# Digital_Output.net
KiCad netlist of a schematic drawn in Altium Designer
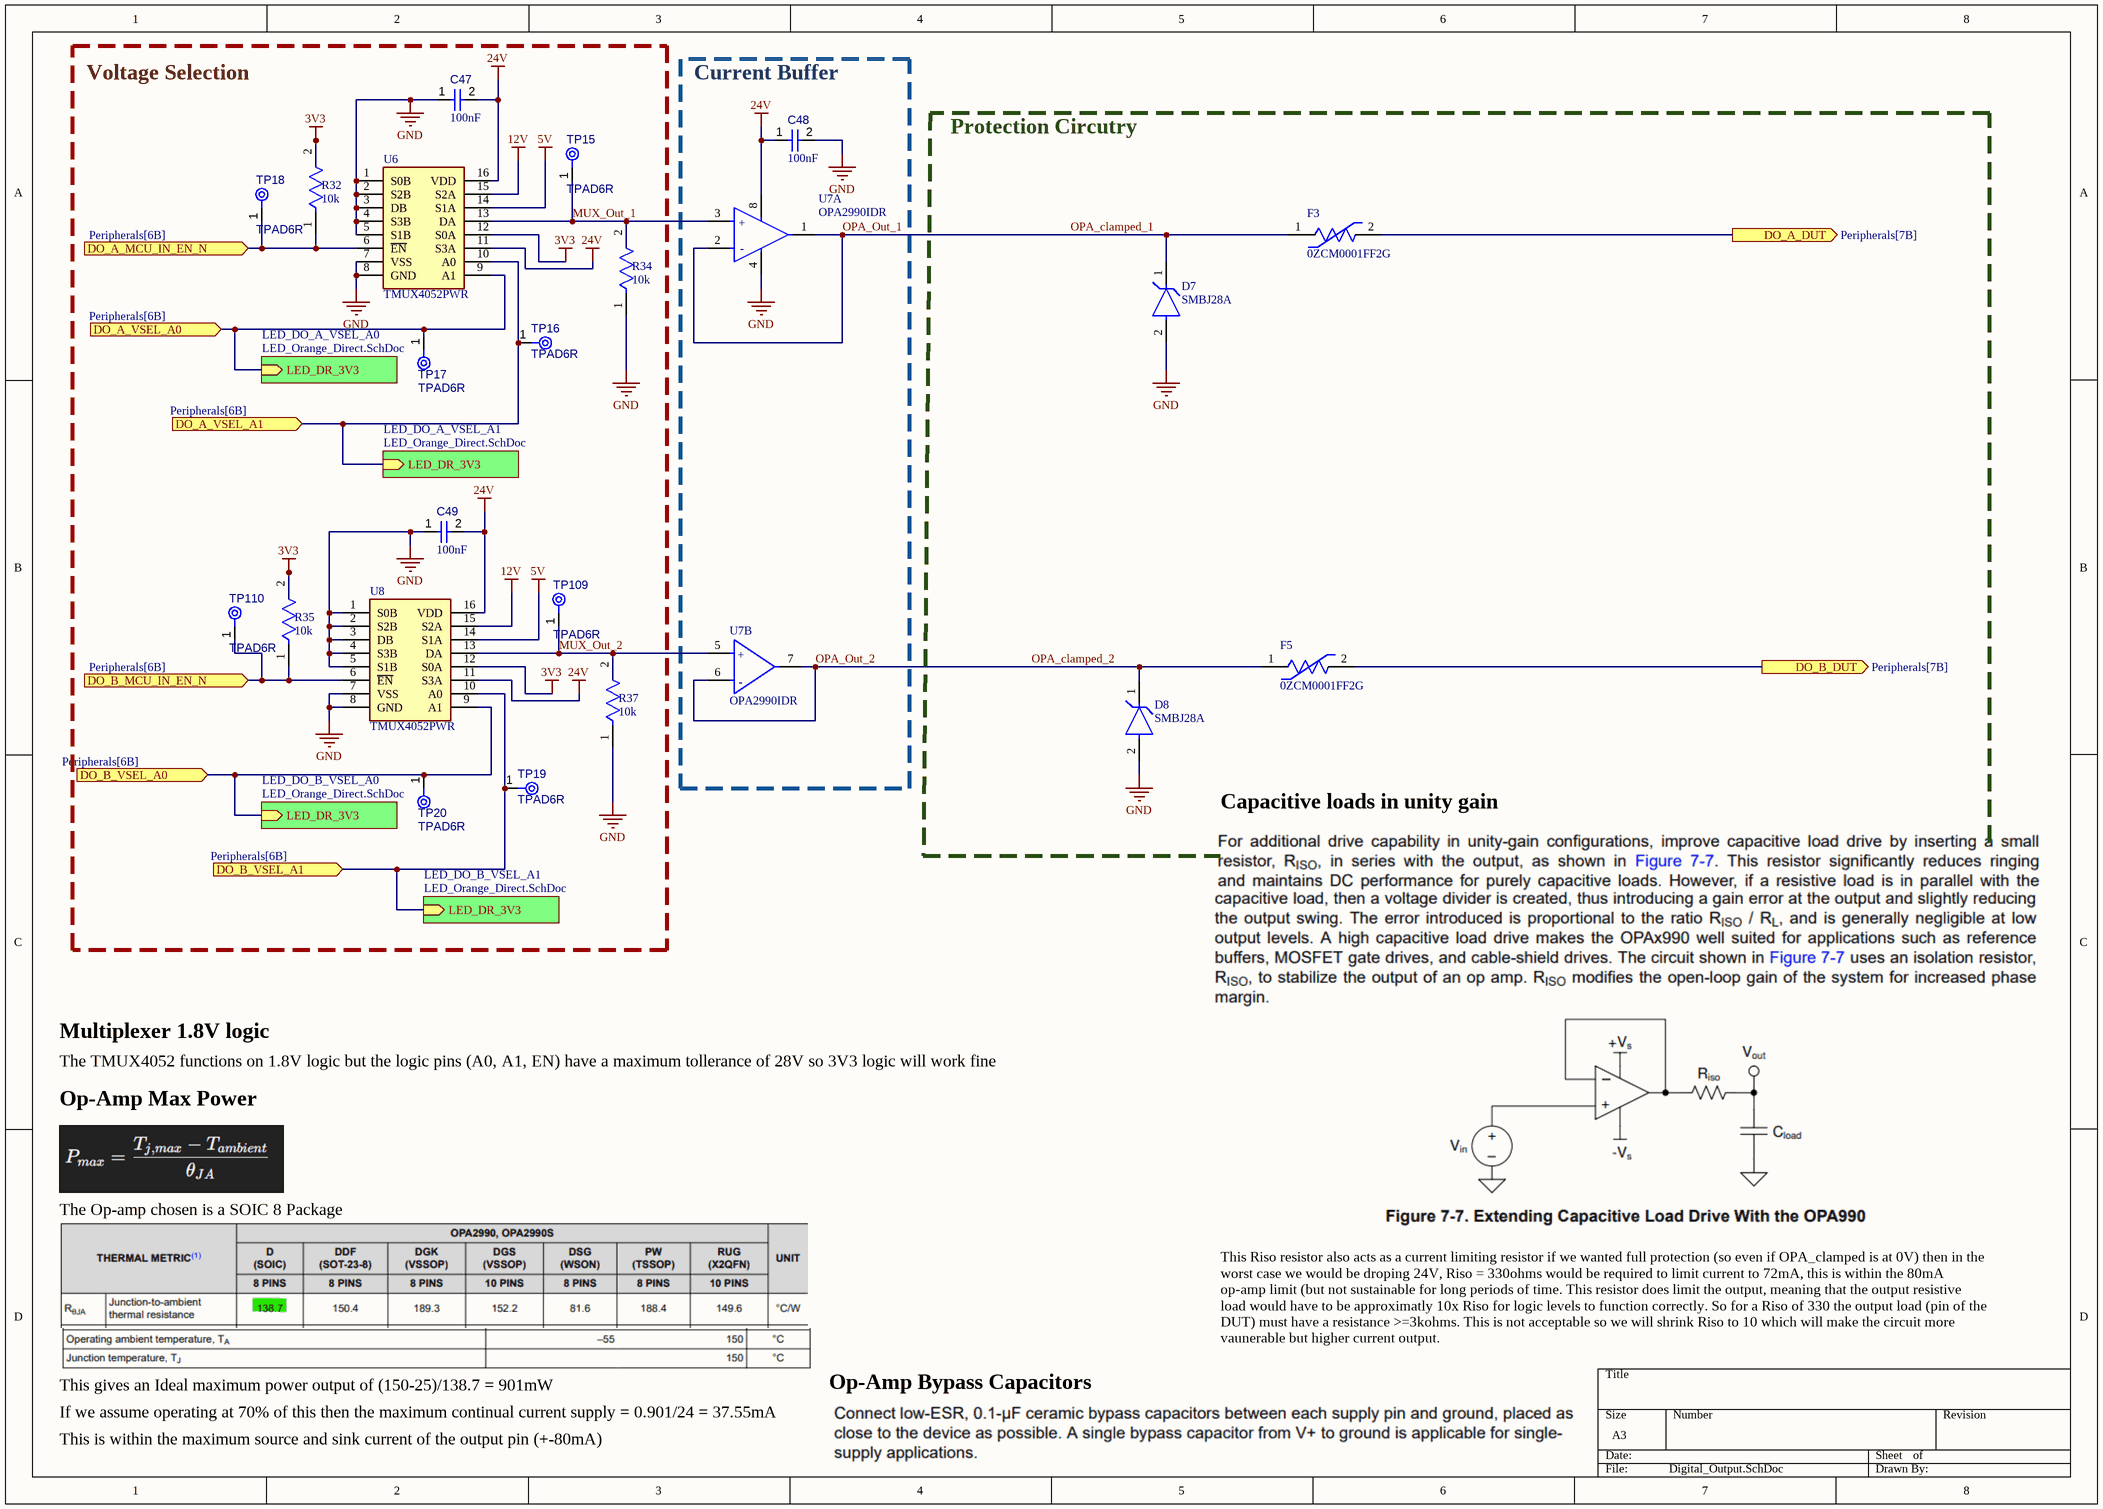
[diagram p0:  Digital_Output.SchDoc]

(export (version "E")
  (design (tool "Eeschema 10.0.6"))
  (components
    (comp (ref "C47")
      (value "100nF")
      (footprint "CAPC1608X90X40NL10T20")
      (description "Chip Capacitor, 100 nF, +/- 10%, 50 V, 0603 (1608 Metric)")
      (fields (field (name "TOLERANCE") "10%") (field (name "Comment") "Capacitor 100 nF +/-10% 50 V 0603"))
      (libsource (lib "HIL RIG FYP") (part "CAP-NP-2"))
    )
    (comp (ref "C48")
      (value "100nF")
      (footprint "CAPC1608X90X40NL10T20")
      (description "Chip Capacitor, 100 nF, +/- 10%, 50 V, 0603 (1608 Metric)")
      (fields (field (name "TOLERANCE") "10%") (field (name "Comment") "Capacitor 100 nF +/-10% 50 V 0603"))
      (libsource (lib "HIL RIG FYP") (part "CAP-NP-2"))
    )
    (comp (ref "C49")
      (value "100nF")
      (footprint "CAPC1608X90X40NL10T20")
      (description "Chip Capacitor, 100 nF, +/- 10%, 50 V, 0603 (1608 Metric)")
      (fields (field (name "TOLERANCE") "10%") (field (name "Comment") "Capacitor 100 nF +/-10% 50 V 0603"))
      (libsource (lib "HIL RIG FYP") (part "CAP-NP-2"))
    )
    (comp (ref "D7")
      (value "SMBJ28A")
      (footprint "FP-SMBJ-MFG")
      (description "Tvs Diodes & Esd Suppressors; SMBJ28A; Littelfuse; 28 V; 45.4 V; 31.1 V; 31.1 V")
      (fields (field (name "VOLTAGE") "28V"))
      (libsource (lib "HIL RIG FYP") (part "f813f71cba58e380607f5dd3caf9714"))
    )
    (comp (ref "D8")
      (value "SMBJ28A")
      (footprint "FP-SMBJ-MFG")
      (description "Tvs Diodes & Esd Suppressors; SMBJ28A; Littelfuse; 28 V; 45.4 V; 31.1 V; 31.1 V")
      (fields (field (name "VOLTAGE") "28V"))
      (libsource (lib "HIL RIG FYP") (part "f813f71cba58e380607f5dd3caf9714"))
    )
    (comp (ref "F3")
      (value "0ZCM0001FF2G")
      (footprint "FP-0ZCM0001FF2G-MFG")
      (description "Prices include import duty and tax. RESETTABLE PTC FUSE, SMD, 0603 SIZE, 10MA, 60V;")
      (libsource (lib "HIL RIG FYP") (part "1c6d77a0208143737455a0c7eb396be"))
    )
    (comp (ref "F5")
      (value "0ZCM0001FF2G")
      (footprint "FP-0ZCM0001FF2G-MFG")
      (description "Prices include import duty and tax. RESETTABLE PTC FUSE, SMD, 0603 SIZE, 10MA, 60V;")
      (libsource (lib "HIL RIG FYP") (part "1c6d77a0208143737455a0c7eb396be"))
    )
    (comp (ref "R32")
      (value "10k")
      (footprint "FP-RT0603-IPC_C")
      (description "Res Thin Film 0603 10K Ohm 0.1% 1/10W ¦25ppm/¦C SMD Paper T/R")
      (fields (field (name "TOLERANCE") "0.1%") (field (name "Comment") "RT0603BRD0710KL"))
      (libsource (lib "HIL RIG FYP") (part "1029c3af85768c4190bb7ad29bc67b5"))
    )
    (comp (ref "R34")
      (value "10k")
      (footprint "FP-RT0603-IPC_C")
      (description "Res Thin Film 0603 10K Ohm 0.1% 1/10W ¦25ppm/¦C SMD Paper T/R")
      (fields (field (name "TOLERANCE") "0.1%") (field (name "Comment") "RT0603BRD0710KL"))
      (libsource (lib "HIL RIG FYP") (part "1029c3af85768c4190bb7ad29bc67b5"))
    )
    (comp (ref "R35")
      (value "10k")
      (footprint "FP-RT0603-IPC_C")
      (description "Res Thin Film 0603 10K Ohm 0.1% 1/10W ¦25ppm/¦C SMD Paper T/R")
      (fields (field (name "TOLERANCE") "0.1%") (field (name "Comment") "RT0603BRD0710KL"))
      (libsource (lib "HIL RIG FYP") (part "1029c3af85768c4190bb7ad29bc67b5"))
    )
    (comp (ref "R37")
      (value "10k")
      (footprint "FP-RT0603-IPC_C")
      (description "Res Thin Film 0603 10K Ohm 0.1% 1/10W ¦25ppm/¦C SMD Paper T/R")
      (fields (field (name "TOLERANCE") "0.1%") (field (name "Comment") "RT0603BRD0710KL"))
      (libsource (lib "HIL RIG FYP") (part "1029c3af85768c4190bb7ad29bc67b5"))
    )
    (comp (ref "TP15")
      (value "TPAD6R")
      (footprint "TP06R")
      (description "0.6mm round")
      (libsource (lib "HIL RIG FYP") (part "CMP-001-0001-4"))
    )
    (comp (ref "TP16")
      (value "TPAD6R")
      (footprint "TP06R")
      (description "0.6mm round")
      (libsource (lib "HIL RIG FYP") (part "CMP-001-0001-4"))
    )
    (comp (ref "TP17")
      (value "TPAD6R")
      (footprint "TP06R")
      (description "0.6mm round")
      (libsource (lib "HIL RIG FYP") (part "CMP-001-0001-4"))
    )
    (comp (ref "TP18")
      (value "TPAD6R")
      (footprint "TP06R")
      (description "0.6mm round")
      (libsource (lib "HIL RIG FYP") (part "CMP-001-0001-4"))
    )
    (comp (ref "TP19")
      (value "TPAD6R")
      (footprint "TP06R")
      (description "0.6mm round")
      (libsource (lib "HIL RIG FYP") (part "CMP-001-0001-4"))
    )
    (comp (ref "TP20")
      (value "TPAD6R")
      (footprint "TP06R")
      (description "0.6mm round")
      (libsource (lib "HIL RIG FYP") (part "CMP-001-0001-4"))
    )
    (comp (ref "TP109")
      (value "TPAD6R")
      (footprint "TP06R")
      (description "0.6mm round")
      (libsource (lib "HIL RIG FYP") (part "CMP-001-0001-4"))
    )
    (comp (ref "TP110")
      (value "TPAD6R")
      (footprint "TP06R")
      (description "0.6mm round")
      (libsource (lib "HIL RIG FYP") (part "CMP-001-0001-4"))
    )
    (comp (ref "U6")
      (value "TMUX4052PWR")
      (footprint "SOP65P640X120-16N")
      (description "Texas Instruments")
      (fields (field (name "MOUSER PART NUMBER") "595-TMUX4052PWR"))
      (libsource (lib "HIL RIG FYP") (part "TMUX4052PWR"))
    )
    (comp (ref "U7")
      (value "OPA2990IDR")
      (footprint "FP-D0008A-IPC_A")
      (description "IC OPAMP GP 2 CIRCUIT 8SOIC / General Purpose Amplifier 2 Circuit Rail-to-Rail 8-SOIC")
      (libsource (lib "HIL RIG FYP") (part "d5b36c1049528187b1d2197d5d58d7e"))
    )
    (comp (ref "U8")
      (value "TMUX4052PWR")
      (footprint "SOP65P640X120-16N")
      (description "Texas Instruments")
      (fields (field (name "MOUSER PART NUMBER") "595-TMUX4052PWR"))
      (libsource (lib "HIL RIG FYP") (part "TMUX4052PWR"))
    )
  )
  (nets
    (net (code "1") (name "/DO_A_DUT") (class "Default")
      (node (ref "F3") (pin "2") (pinfunction "2_2") (pintype "passive"))
    )
    (net (code "2") (name "/DO_A_MCU_IN_EN_N") (class "Default")
      (node (ref "R32") (pin "1") (pinfunction "1_1") (pintype "passive"))
      (node (ref "TP18") (pin "1") (pinfunction "TP_1") (pintype "passive"))
      (node (ref "U6") (pin "6") (pinfunction "~{EN}_6") (pintype "passive"))
    )
    (net (code "3") (name "/DO_A_VSEL_A0") (class "Default")
      (node (ref "TP17") (pin "1") (pinfunction "TP_1") (pintype "passive"))
      (node (ref "U6") (pin "9") (pinfunction "A1_9") (pintype "passive"))
    )
    (net (code "4") (name "/DO_A_VSEL_A1") (class "Default")
      (node (ref "TP16") (pin "1") (pinfunction "TP_1") (pintype "passive"))
      (node (ref "U6") (pin "10") (pinfunction "A0_10") (pintype "passive"))
    )
    (net (code "5") (name "/DO_B_DUT") (class "Default")
      (node (ref "F5") (pin "2") (pinfunction "2_2") (pintype "passive"))
    )
    (net (code "6") (name "/DO_B_MCU_IN_EN_N") (class "Default")
      (node (ref "R35") (pin "1") (pinfunction "1_1") (pintype "passive"))
      (node (ref "TP110") (pin "1") (pinfunction "TP_1") (pintype "passive"))
      (node (ref "U8") (pin "6") (pinfunction "~{EN}_6") (pintype "passive"))
    )
    (net (code "7") (name "/DO_B_VSEL_A0") (class "Default")
      (node (ref "TP20") (pin "1") (pinfunction "TP_1") (pintype "passive"))
      (node (ref "U8") (pin "9") (pinfunction "A1_9") (pintype "passive"))
    )
    (net (code "8") (name "/DO_B_VSEL_A1") (class "Default")
      (node (ref "TP19") (pin "1") (pinfunction "TP_1") (pintype "passive"))
      (node (ref "U8") (pin "10") (pinfunction "A0_10") (pintype "passive"))
    )
    (net (code "9") (name "/MUX_Out_1") (class "Default")
      (node (ref "R34") (pin "2") (pinfunction "2_2") (pintype "passive"))
      (node (ref "TP15") (pin "1") (pinfunction "TP_1") (pintype "passive"))
      (node (ref "U6") (pin "13") (pinfunction "DA_13") (pintype "passive"))
      (node (ref "U7") (pin "3") (pinfunction "IN1+_3") (pintype "tri_state"))
    )
    (net (code "10") (name "/MUX_Out_2") (class "Default")
      (node (ref "R37") (pin "2") (pinfunction "2_2") (pintype "passive"))
      (node (ref "TP109") (pin "1") (pinfunction "TP_1") (pintype "passive"))
      (node (ref "U7") (pin "5") (pinfunction "IN2+_5") (pintype "tri_state"))
      (node (ref "U8") (pin "13") (pinfunction "DA_13") (pintype "passive"))
    )
    (net (code "11") (name "/OPA_Out_1") (class "Default")
      (node (ref "D7") (pin "1") (pinfunction "C_1") (pintype "passive"))
      (node (ref "F3") (pin "1") (pinfunction "1_1") (pintype "passive"))
      (node (ref "U7") (pin "1") (pinfunction "OUT1_1") (pintype "passive"))
      (node (ref "U7") (pin "2") (pinfunction "IN1-_2") (pintype "tri_state"))
    )
    (net (code "12") (name "/OPA_Out_2") (class "Default")
      (node (ref "D8") (pin "1") (pinfunction "C_1") (pintype "passive"))
      (node (ref "F5") (pin "1") (pinfunction "1_1") (pintype "passive"))
      (node (ref "U7") (pin "6") (pinfunction "IN2-_6") (pintype "tri_state"))
      (node (ref "U7") (pin "7") (pinfunction "OUT2_7") (pintype "passive"))
    )
    (net (code "13") (name "3V3") (class "Default")
      (node (ref "R32") (pin "2") (pinfunction "2_2") (pintype "passive"))
      (node (ref "R35") (pin "2") (pinfunction "2_2") (pintype "passive"))
      (node (ref "U6") (pin "12") (pinfunction "S0A_12") (pintype "passive"))
      (node (ref "U8") (pin "12") (pinfunction "S0A_12") (pintype "passive"))
    )
    (net (code "14") (name "5V") (class "Default")
      (node (ref "U6") (pin "14") (pinfunction "S1A_14") (pintype "passive"))
      (node (ref "U8") (pin "14") (pinfunction "S1A_14") (pintype "passive"))
    )
    (net (code "15") (name "12V") (class "Default")
      (node (ref "U6") (pin "15") (pinfunction "S2A_15") (pintype "passive"))
      (node (ref "U8") (pin "15") (pinfunction "S2A_15") (pintype "passive"))
    )
    (net (code "16") (name "24V") (class "Default")
      (node (ref "C47") (pin "2") (pinfunction "2_2") (pintype "passive"))
      (node (ref "C48") (pin "1") (pinfunction "1_1") (pintype "passive"))
      (node (ref "C49") (pin "2") (pinfunction "2_2") (pintype "passive"))
      (node (ref "U6") (pin "11") (pinfunction "S3A_11") (pintype "passive"))
      (node (ref "U6") (pin "16") (pinfunction "VDD_16") (pintype "passive"))
      (node (ref "U7") (pin "8") (pinfunction "V+_8") (pintype "power_in"))
      (node (ref "U8") (pin "11") (pinfunction "S3A_11") (pintype "passive"))
      (node (ref "U8") (pin "16") (pinfunction "VDD_16") (pintype "passive"))
    )
    (net (code "17") (name "GND") (class "Default")
      (node (ref "C47") (pin "1") (pinfunction "1_1") (pintype "passive"))
      (node (ref "C48") (pin "2") (pinfunction "2_2") (pintype "passive"))
      (node (ref "C49") (pin "1") (pinfunction "1_1") (pintype "passive"))
      (node (ref "D7") (pin "2") (pinfunction "A_2") (pintype "passive"))
      (node (ref "D8") (pin "2") (pinfunction "A_2") (pintype "passive"))
      (node (ref "R34") (pin "1") (pinfunction "1_1") (pintype "passive"))
      (node (ref "R37") (pin "1") (pinfunction "1_1") (pintype "passive"))
      (node (ref "U6") (pin "1") (pinfunction "S0B_1") (pintype "passive"))
      (node (ref "U6") (pin "2") (pinfunction "S2B_2") (pintype "passive"))
      (node (ref "U6") (pin "3") (pinfunction "DB_3") (pintype "passive"))
      (node (ref "U6") (pin "4") (pinfunction "S3B_4") (pintype "passive"))
      (node (ref "U6") (pin "5") (pinfunction "S1B_5") (pintype "passive"))
      (node (ref "U6") (pin "7") (pinfunction "VSS_7") (pintype "passive"))
      (node (ref "U6") (pin "8") (pinfunction "GND_8") (pintype "passive"))
      (node (ref "U7") (pin "4") (pinfunction "V-_4") (pintype "power_in"))
      (node (ref "U8") (pin "1") (pinfunction "S0B_1") (pintype "passive"))
      (node (ref "U8") (pin "2") (pinfunction "S2B_2") (pintype "passive"))
      (node (ref "U8") (pin "3") (pinfunction "DB_3") (pintype "passive"))
      (node (ref "U8") (pin "4") (pinfunction "S3B_4") (pintype "passive"))
      (node (ref "U8") (pin "5") (pinfunction "S1B_5") (pintype "passive"))
      (node (ref "U8") (pin "7") (pinfunction "VSS_7") (pintype "passive"))
      (node (ref "U8") (pin "8") (pinfunction "GND_8") (pintype "passive"))
    )
  )
)
